# schema.net
KiCad netlist of a schematic drawn in EAGLE
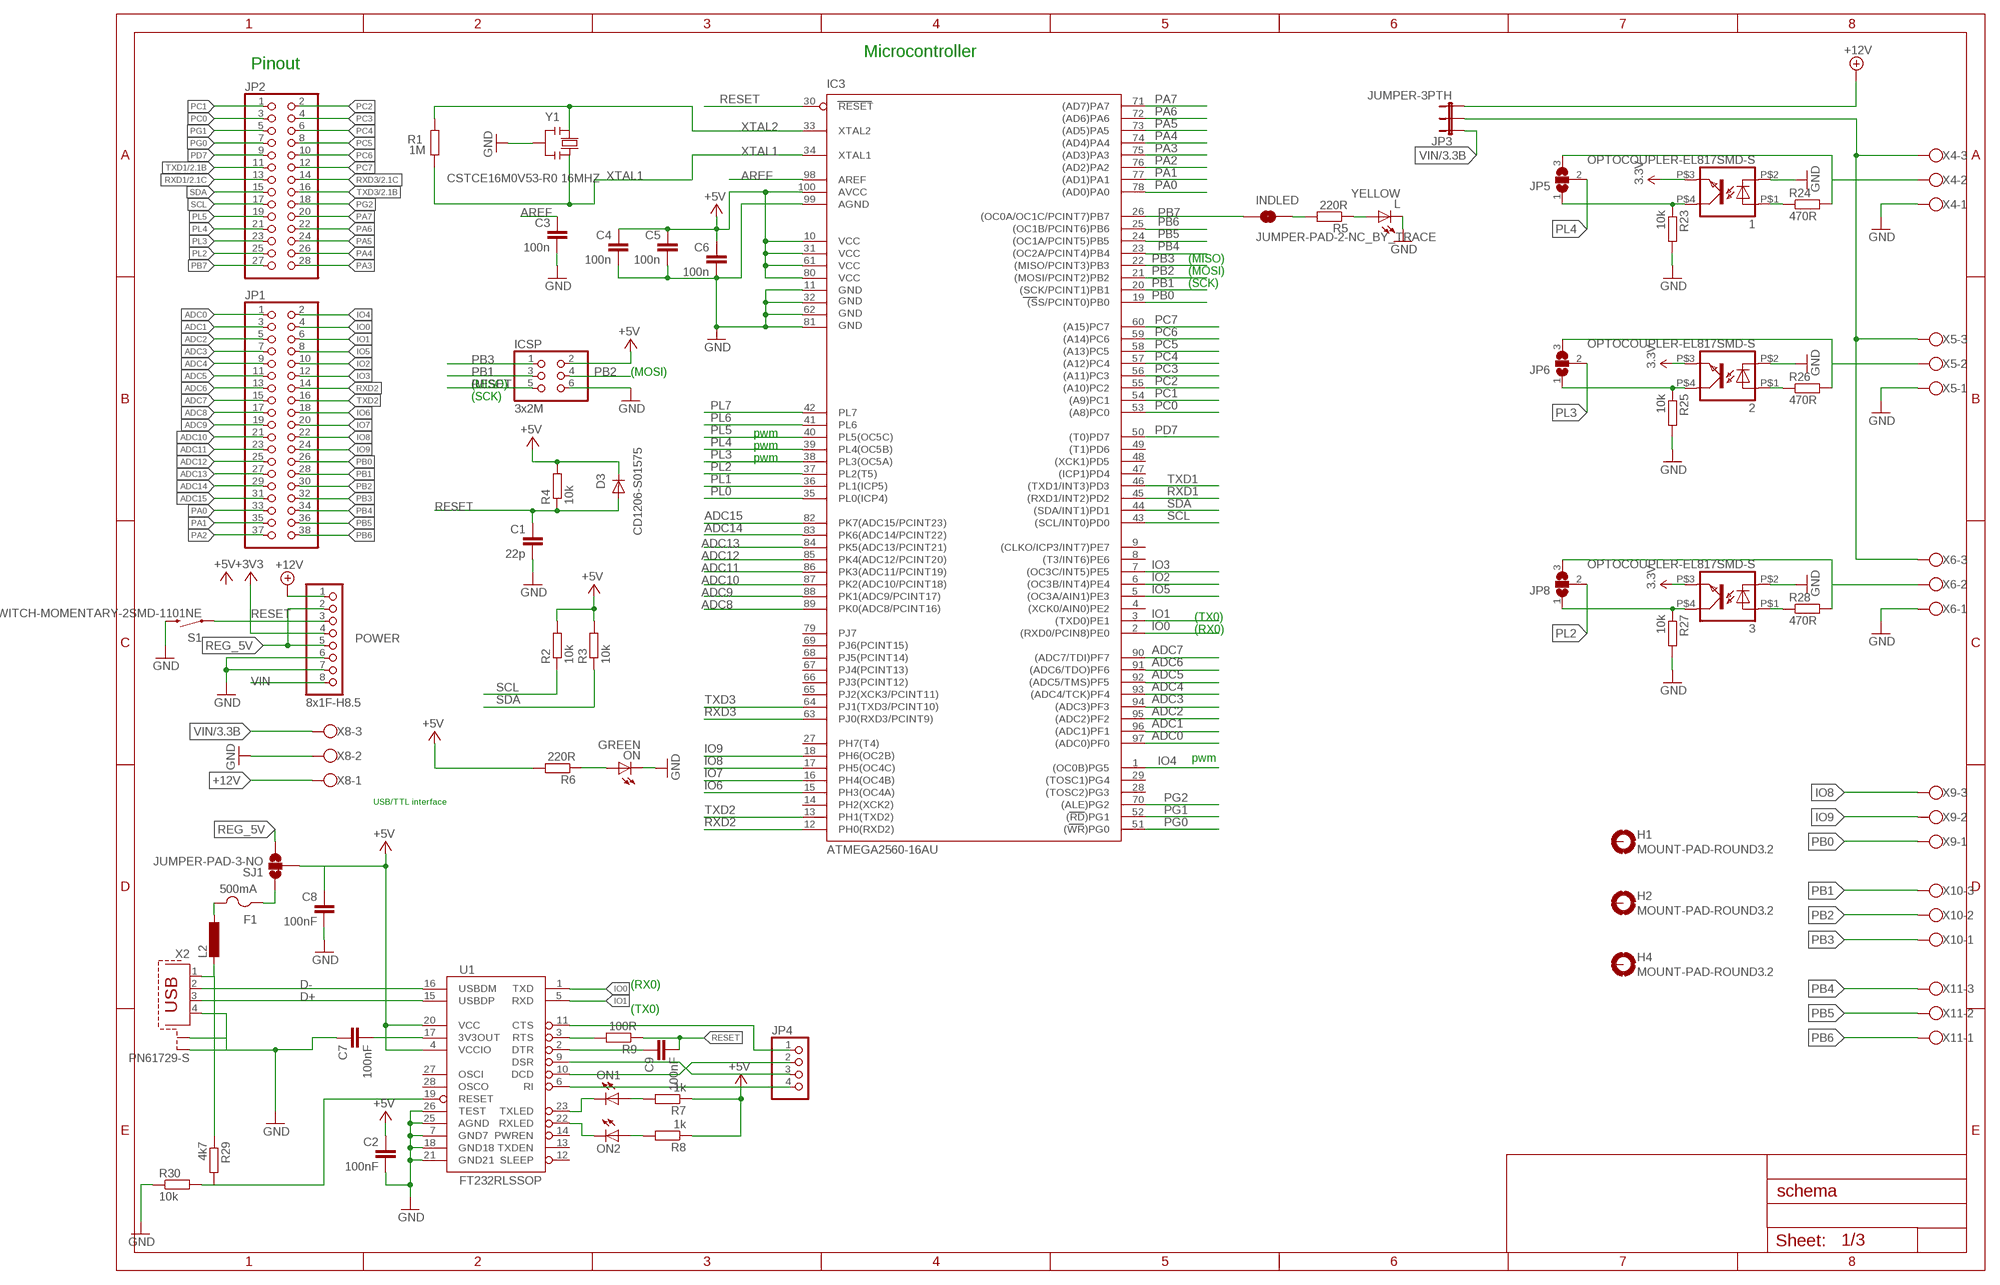
[diagram p0: schematic, sheet 1]
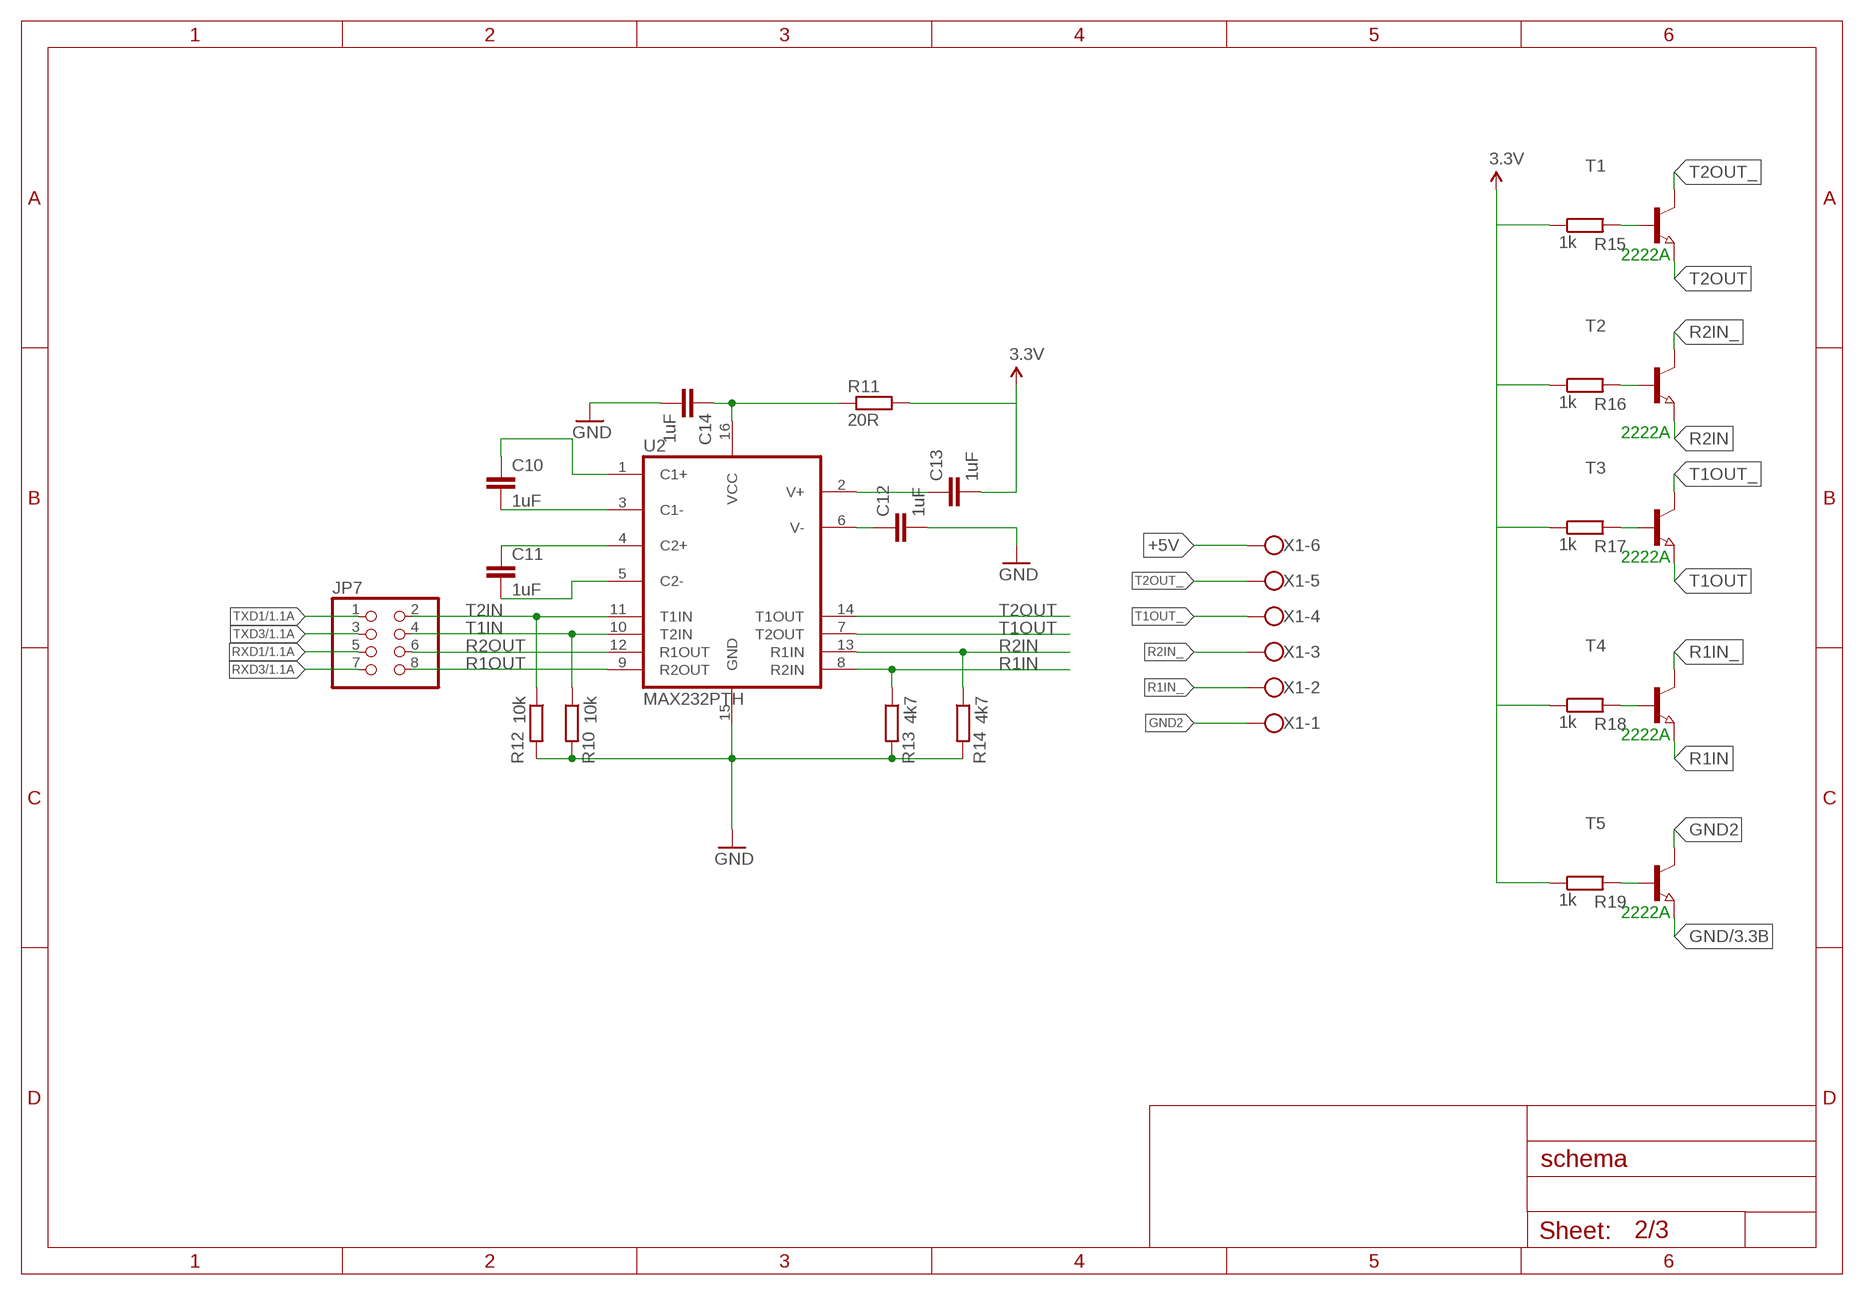
[diagram p1: schematic, sheet 2]
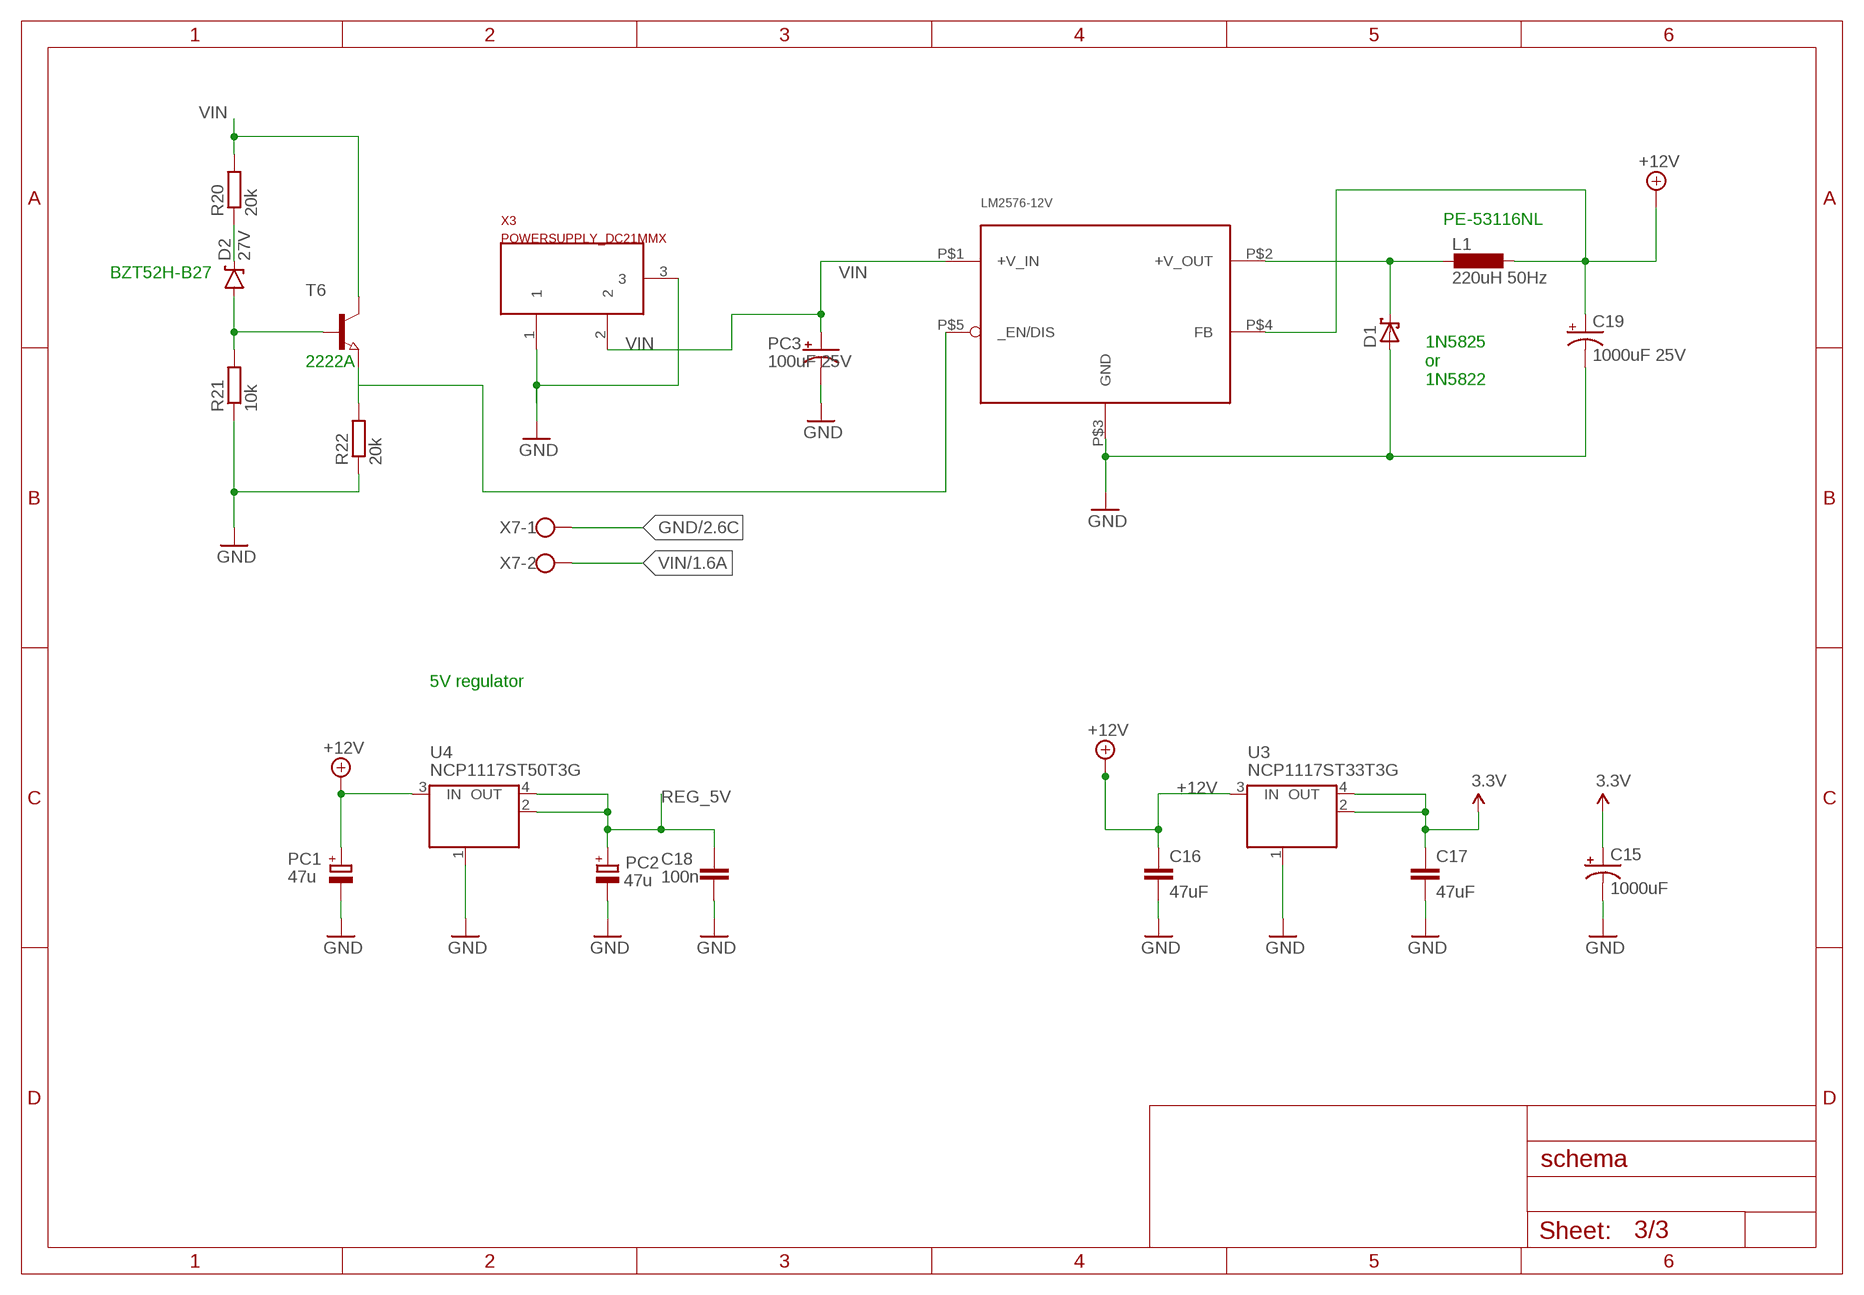
[diagram p2: schematic, sheet 3]

(export (version "E")
  (design (tool "Eeschema 10.0.6"))
  (components
    (comp (ref "C15")
      (value "1000uF")
      (footprint "eagle-import:E5-6")
      (libsource (lib "eagle-import") (part "CPOL-USE5-6"))
    )
    (comp (ref "C16")
      (value "47uF")
      (footprint "eagle-import:C0603")
      (libsource (lib "eagle-import") (part "rcl_C-EUC0603"))
    )
    (comp (ref "C17")
      (value "47uF")
      (footprint "eagle-import:C0603")
      (libsource (lib "eagle-import") (part "rcl_C-EUC0603"))
    )
    (comp (ref "C18")
      (value "100n")
      (footprint "eagle-import:C0603-ROUND")
      (libsource (lib "eagle-import") (part "C-EU0603-RND"))
    )
    (comp (ref "C19")
      (value "1000uF 25V")
      (footprint "eagle-import:E5-6")
      (libsource (lib "eagle-import") (part "CPOL-USE5-6"))
    )
    (comp (ref "D1")
      (value "1N5908")
      (footprint "eagle-import:C4111-15")
      (libsource (lib "eagle-import") (part "1N5908"))
    )
    (comp (ref "D2")
      (value "27V")
      (footprint "eagle-import:SOD-123")
      (libsource (lib "eagle-import") (part "DIODE-ZENER16V"))
    )
    (comp (ref "L1")
      (value "220uH 50Hz")
      (footprint "eagle-import:KM-4.0")
      (libsource (lib "eagle-import") (part "L-KM4.0"))
    )
    (comp (ref "LM2576-12V")
      (value "LM2576-T05D")
      (footprint "eagle-import:TO220-5_STAGGERED")
      (libsource (lib "eagle-import") (part "LM2576-T05D"))
    )
    (comp (ref "PC1")
      (value "47u")
      (footprint "eagle-import:PANASONIC_D")
      (libsource (lib "eagle-import") (part "CPOL-EUD"))
    )
    (comp (ref "PC2")
      (value "47u")
      (footprint "eagle-import:PANASONIC_D")
      (libsource (lib "eagle-import") (part "CPOL-EUD"))
    )
    (comp (ref "PC3")
      (value "100uF 25V")
      (footprint "eagle-import:E5-6")
      (libsource (lib "eagle-import") (part "CPOL-USE5-6"))
    )
    (comp (ref "R20")
      (value "20k")
      (footprint "eagle-import:R0603")
      (libsource (lib "eagle-import") (part "rcl_R-EU_R0603"))
    )
    (comp (ref "R21")
      (value "10k")
      (footprint "eagle-import:R0603")
      (libsource (lib "eagle-import") (part "rcl_R-EU_R0603"))
    )
    (comp (ref "R22")
      (value "20k")
      (footprint "eagle-import:R0603")
      (libsource (lib "eagle-import") (part "rcl_R-EU_R0603"))
    )
    (comp (ref "T6")
      (value "NPN-TRANSISTOR_SOT23")
      (footprint "eagle-import:SOT23")
      (libsource (lib "eagle-import") (part "NPN-TRANSISTOR_SOT23"))
    )
    (comp (ref "U3")
      (value "NCP1117ST33T3G")
      (footprint "eagle-import:SOT223")
      (libsource (lib "eagle-import") (part "MC33269ST-3.3T3"))
    )
    (comp (ref "U4")
      (value "NCP1117ST50T3G")
      (footprint "eagle-import:SOT223")
      (libsource (lib "eagle-import") (part "MC33269ST-3.3T3"))
    )
    (comp (ref "X3")
      (value "POWERSUPPLY_DC21MMX")
      (footprint "eagle-import:POWERSUPPLY_DC-21MM")
      (libsource (lib "eagle-import") (part "POWERSUPPLY_DC21MMX"))
    )
    (comp (ref "X7")
      (value "W237-102")
      (footprint "eagle-import:W237-102")
      (fields (field (name "MPN") "237-102"))
      (libsource (lib "eagle-import") (part "W237-102"))
    )
    (comp (ref "1")
      (value "OPTOCOUPLER-EL817SMD-S")
      (footprint "eagle-import:SMD-S")
      (libsource (lib "eagle-import") (part "OPTOCOUPLER-EL817SMD-S"))
    )
    (comp (ref "2")
      (value "OPTOCOUPLER-EL817SMD-S")
      (footprint "eagle-import:SMD-S")
      (libsource (lib "eagle-import") (part "OPTOCOUPLER-EL817SMD-S"))
    )
    (comp (ref "3")
      (value "OPTOCOUPLER-EL817SMD-S")
      (footprint "eagle-import:SMD-S")
      (libsource (lib "eagle-import") (part "OPTOCOUPLER-EL817SMD-S"))
    )
    (comp (ref "C1")
      (value "22p")
      (footprint "eagle-import:C0603-ROUND")
      (libsource (lib "eagle-import") (part "C-EU0603-RND"))
    )
    (comp (ref "C2")
      (value "100nF")
      (footprint "eagle-import:C0603-ROUND")
      (libsource (lib "eagle-import") (part "C-EU0603-RND"))
    )
    (comp (ref "C3")
      (value "100n")
      (footprint "eagle-import:C0603-ROUND")
      (libsource (lib "eagle-import") (part "C-EU0603-RND"))
    )
    (comp (ref "C4")
      (value "100n")
      (footprint "eagle-import:C0603-ROUND")
      (libsource (lib "eagle-import") (part "C-EU0603-RND"))
    )
    (comp (ref "C5")
      (value "100n")
      (footprint "eagle-import:C0603-ROUND")
      (libsource (lib "eagle-import") (part "C-EU0603-RND"))
    )
    (comp (ref "C6")
      (value "100n")
      (footprint "eagle-import:C0603-ROUND")
      (libsource (lib "eagle-import") (part "C-EU0603-RND"))
    )
    (comp (ref "C7")
      (value "100nF")
      (footprint "eagle-import:C0603-ROUND")
      (libsource (lib "eagle-import") (part "C-EU0603-RND"))
    )
    (comp (ref "C8")
      (value "100nF")
      (footprint "eagle-import:C0603-ROUND")
      (libsource (lib "eagle-import") (part "C-EU0603-RND"))
    )
    (comp (ref "C9")
      (value "100nF")
      (footprint "eagle-import:C0603-ROUND")
      (libsource (lib "eagle-import") (part "C-EU0603-RND"))
    )
    (comp (ref "D3")
      (value "CD1206-S01575")
      (footprint "eagle-import:MINIMELF")
      (libsource (lib "eagle-import") (part "DIODE-MINIMELF"))
    )
    (comp (ref "F1")
      (value "500mA")
      (footprint "eagle-import:1812")
      (libsource (lib "eagle-import") (part "PTCFUSE-1812"))
    )
    (comp (ref "H1")
      (value "MOUNT-PAD-ROUND3.2")
      (footprint "eagle-import:3,2-PAD")
      (libsource (lib "eagle-import") (part "MOUNT-PAD-ROUND3.2"))
    )
    (comp (ref "H2")
      (value "MOUNT-PAD-ROUND3.2")
      (footprint "eagle-import:3,2-PAD")
      (libsource (lib "eagle-import") (part "MOUNT-PAD-ROUND3.2"))
    )
    (comp (ref "H4")
      (value "MOUNT-PAD-ROUND3.2")
      (footprint "eagle-import:3,2-PAD")
      (libsource (lib "eagle-import") (part "MOUNT-PAD-ROUND3.2"))
    )
    (comp (ref "IC3")
      (value "ATMEGA2560-16AU")
      (footprint "eagle-import:TQFP100")
      (libsource (lib "eagle-import") (part "ATMEGA2560AU2560-16"))
    )
    (comp (ref "ICSP")
      (value "3x2M")
      (footprint "eagle-import:2X03")
      (libsource (lib "eagle-import") (part "PINHD-2X3"))
    )
    (comp (ref "INDLED")
      (value "JUMPER-PAD-2-NC_BY_TRACE")
      (footprint "eagle-import:PAD-JUMPER-2-NC_BY_TRACE_YES_SILK")
      (libsource (lib "eagle-import") (part "JUMPER-PAD-2-NC_BY_TRACE"))
    )
    (comp (ref "JP1")
      (value "PINHD-2X19")
      (footprint "eagle-import:2X19")
      (libsource (lib "eagle-import") (part "PINHD-2X19"))
    )
    (comp (ref "JP2")
      (value "PINHD-2X14")
      (footprint "eagle-import:2X14")
      (libsource (lib "eagle-import") (part "PINHD-2X14"))
    )
    (comp (ref "JP3")
      (value "JUMPER-3PTH")
      (footprint "eagle-import:1X03")
      (libsource (lib "eagle-import") (part "JUMPER-3PTH"))
    )
    (comp (ref "JP4")
      (value "PINHD-1X4")
      (footprint "eagle-import:1X04")
      (libsource (lib "eagle-import") (part "PINHD-1X4"))
    )
    (comp (ref "JP5")
      (value "SJ2W")
      (footprint "eagle-import:SJ_2")
      (libsource (lib "eagle-import") (part "SJ2W"))
    )
    (comp (ref "JP6")
      (value "SJ2W")
      (footprint "eagle-import:SJ_2")
      (libsource (lib "eagle-import") (part "SJ2W"))
    )
    (comp (ref "JP8")
      (value "SJ2W")
      (footprint "eagle-import:SJ_2")
      (libsource (lib "eagle-import") (part "SJ2W"))
    )
    (comp (ref "L")
      (value "YELLOW")
      (footprint "eagle-import:CHIP-LED0805")
      (libsource (lib "eagle-import") (part "LEDCHIP-LED0805"))
    )
    (comp (ref "L2")
      (value "L-EUL1812")
      (footprint "eagle-import:L1812")
      (libsource (lib "eagle-import") (part "L-EUL1812"))
    )
    (comp (ref "ON")
      (value "GREEN")
      (footprint "eagle-import:CHIP-LED0805")
      (libsource (lib "eagle-import") (part "LEDCHIP-LED0805"))
    )
    (comp (ref "ON1")
      (value "GREEN")
      (footprint "eagle-import:CHIP-LED0805")
      (libsource (lib "eagle-import") (part "LEDCHIP-LED0805"))
    )
    (comp (ref "ON2")
      (value "GREEN")
      (footprint "eagle-import:CHIP-LED0805")
      (libsource (lib "eagle-import") (part "LEDCHIP-LED0805"))
    )
    (comp (ref "POWER")
      (value "8x1F-H8.5")
      (footprint "eagle-import:1X08")
      (libsource (lib "eagle-import") (part "PINHD-1X8"))
    )
    (comp (ref "R1")
      (value "1M")
      (footprint "eagle-import:R0603-ROUND")
      (libsource (lib "eagle-import") (part "R-EU_R0603"))
    )
    (comp (ref "R2")
      (value "10k")
      (footprint "eagle-import:R0603")
      (libsource (lib "eagle-import") (part "resistor_R-EU_R0603"))
    )
    (comp (ref "R3")
      (value "10k")
      (footprint "eagle-import:R0603")
      (libsource (lib "eagle-import") (part "resistor_R-EU_R0603"))
    )
    (comp (ref "R4")
      (value "10k")
      (footprint "eagle-import:R0603")
      (libsource (lib "eagle-import") (part "resistor_R-EU_R0603"))
    )
    (comp (ref "R5")
      (value "220R")
      (footprint "eagle-import:R0603")
      (libsource (lib "eagle-import") (part "resistor_R-EU_R0603"))
    )
    (comp (ref "R6")
      (value "220R")
      (footprint "eagle-import:R0603")
      (libsource (lib "eagle-import") (part "resistor_R-EU_R0603"))
    )
    (comp (ref "R7")
      (value "1k")
      (footprint "eagle-import:R0603")
      (libsource (lib "eagle-import") (part "resistor_R-EU_R0603"))
    )
    (comp (ref "R8")
      (value "1k")
      (footprint "eagle-import:R0603")
      (libsource (lib "eagle-import") (part "resistor_R-EU_R0603"))
    )
    (comp (ref "R9")
      (value "100R")
      (footprint "eagle-import:R0603")
      (libsource (lib "eagle-import") (part "resistor_R-EU_R0603"))
    )
    (comp (ref "R23")
      (value "10k")
      (footprint "eagle-import:R0603")
      (libsource (lib "eagle-import") (part "resistor_R-EU_R0603"))
    )
    (comp (ref "R24")
      (value "470R")
      (footprint "eagle-import:R0603")
      (libsource (lib "eagle-import") (part "resistor_R-EU_R0603"))
    )
    (comp (ref "R25")
      (value "10k")
      (footprint "eagle-import:R0603")
      (libsource (lib "eagle-import") (part "resistor_R-EU_R0603"))
    )
    (comp (ref "R26")
      (value "470R")
      (footprint "eagle-import:R0603")
      (libsource (lib "eagle-import") (part "resistor_R-EU_R0603"))
    )
    (comp (ref "R27")
      (value "10k")
      (footprint "eagle-import:R0603")
      (libsource (lib "eagle-import") (part "resistor_R-EU_R0603"))
    )
    (comp (ref "R28")
      (value "470R")
      (footprint "eagle-import:R0603")
      (libsource (lib "eagle-import") (part "resistor_R-EU_R0603"))
    )
    (comp (ref "R29")
      (value "4k7")
      (footprint "eagle-import:R0603")
      (libsource (lib "eagle-import") (part "resistor_R-EU_R0603"))
    )
    (comp (ref "R30")
      (value "10k")
      (footprint "eagle-import:R0603")
      (libsource (lib "eagle-import") (part "resistor_R-EU_R0603"))
    )
    (comp (ref "S1")
      (value "SWITCH-MOMENTARY-2SMD-1101NE")
      (footprint "eagle-import:TACTILE-SWITCH-1101NE")
      (libsource (lib "eagle-import") (part "SWITCH-MOMENTARY-2SMD-1101NE"))
    )
    (comp (ref "SJ1")
      (value "JUMPER-PAD-3-NO")
      (footprint "eagle-import:PAD-JUMPER-3-NO_YES_SILK_FULL_BOX_WIDE_SPACING")
      (libsource (lib "eagle-import") (part "JUMPER-PAD-3-NO"))
    )
    (comp (ref "U1")
      (value "FT232RLSSOP")
      (footprint "eagle-import:SSOP28DB")
      (libsource (lib "eagle-import") (part "FT232RLSSOP"))
    )
    (comp (ref "X2")
      (value "PN61729-S")
      (footprint "eagle-import:PN61729-S")
      (libsource (lib "eagle-import") (part "PN61729-S"))
    )
    (comp (ref "X4")
      (value "W237-103")
      (footprint "eagle-import:W237-103")
      (fields (field (name "MPN") "237-103"))
      (libsource (lib "eagle-import") (part "W237-103"))
    )
    (comp (ref "X5")
      (value "W237-103")
      (footprint "eagle-import:W237-103")
      (fields (field (name "MPN") "237-103"))
      (libsource (lib "eagle-import") (part "W237-103"))
    )
    (comp (ref "X6")
      (value "W237-103")
      (footprint "eagle-import:W237-103")
      (fields (field (name "MPN") "237-103"))
      (libsource (lib "eagle-import") (part "W237-103"))
    )
    (comp (ref "X8")
      (value "W237-103")
      (footprint "eagle-import:W237-103")
      (fields (field (name "MPN") "237-103"))
      (libsource (lib "eagle-import") (part "W237-103"))
    )
    (comp (ref "X9")
      (value "W237-103")
      (footprint "eagle-import:W237-103")
      (fields (field (name "MPN") "237-103"))
      (libsource (lib "eagle-import") (part "W237-103"))
    )
    (comp (ref "X10")
      (value "W237-103")
      (footprint "eagle-import:W237-103")
      (fields (field (name "MPN") "237-103"))
      (libsource (lib "eagle-import") (part "W237-103"))
    )
    (comp (ref "X11")
      (value "W237-103")
      (footprint "eagle-import:W237-103")
      (fields (field (name "MPN") "237-103"))
      (libsource (lib "eagle-import") (part "W237-103"))
    )
    (comp (ref "Y1")
      (value "CSTCE16M0V53-R0 16MHZ")
      (footprint "eagle-import:RESONATOR")
      (libsource (lib "eagle-import") (part "RESONATORMU"))
    )
    (comp (ref "C10")
      (value "1uF")
      (footprint "eagle-import:C0603")
      (libsource (lib "eagle-import") (part "rcl_C-EUC0603"))
    )
    (comp (ref "C11")
      (value "1uF")
      (footprint "eagle-import:C0603")
      (libsource (lib "eagle-import") (part "rcl_C-EUC0603"))
    )
    (comp (ref "C12")
      (value "1uF")
      (footprint "eagle-import:C0603")
      (libsource (lib "eagle-import") (part "rcl_C-EUC0603"))
    )
    (comp (ref "C13")
      (value "1uF")
      (footprint "eagle-import:C0603")
      (libsource (lib "eagle-import") (part "rcl_C-EUC0603"))
    )
    (comp (ref "C14")
      (value "1uF")
      (footprint "eagle-import:C0603")
      (libsource (lib "eagle-import") (part "rcl_C-EUC0603"))
    )
    (comp (ref "JP7")
      (value "PINHD-2X4")
      (footprint "eagle-import:2X04")
      (libsource (lib "eagle-import") (part "PINHD-2X4"))
    )
    (comp (ref "R10")
      (value "10k")
      (footprint "eagle-import:R0603")
      (libsource (lib "eagle-import") (part "rcl_R-EU_R0603"))
    )
    (comp (ref "R11")
      (value "20R")
      (footprint "eagle-import:R0603")
      (libsource (lib "eagle-import") (part "rcl_R-EU_R0603"))
    )
    (comp (ref "R12")
      (value "10k")
      (footprint "eagle-import:R0603")
      (libsource (lib "eagle-import") (part "rcl_R-EU_R0603"))
    )
    (comp (ref "R13")
      (value "4k7")
      (footprint "eagle-import:R0603")
      (libsource (lib "eagle-import") (part "rcl_R-EU_R0603"))
    )
    (comp (ref "R14")
      (value "4k7")
      (footprint "eagle-import:R0603")
      (libsource (lib "eagle-import") (part "rcl_R-EU_R0603"))
    )
    (comp (ref "R15")
      (value "1k")
      (footprint "eagle-import:R0603")
      (libsource (lib "eagle-import") (part "rcl_R-EU_R0603"))
    )
    (comp (ref "R16")
      (value "1k")
      (footprint "eagle-import:R0603")
      (libsource (lib "eagle-import") (part "rcl_R-EU_R0603"))
    )
    (comp (ref "R17")
      (value "1k")
      (footprint "eagle-import:R0603")
      (libsource (lib "eagle-import") (part "rcl_R-EU_R0603"))
    )
    (comp (ref "R18")
      (value "1k")
      (footprint "eagle-import:R0603")
      (libsource (lib "eagle-import") (part "rcl_R-EU_R0603"))
    )
    (comp (ref "R19")
      (value "1k")
      (footprint "eagle-import:R0603")
      (libsource (lib "eagle-import") (part "rcl_R-EU_R0603"))
    )
    (comp (ref "T1")
      (value "NPN-TRANSISTOR_SOT23")
      (footprint "eagle-import:SOT23")
      (libsource (lib "eagle-import") (part "NPN-TRANSISTOR_SOT23"))
    )
    (comp (ref "T2")
      (value "NPN-TRANSISTOR_SOT23")
      (footprint "eagle-import:SOT23")
      (libsource (lib "eagle-import") (part "NPN-TRANSISTOR_SOT23"))
    )
    (comp (ref "T3")
      (value "NPN-TRANSISTOR_SOT23")
      (footprint "eagle-import:SOT23")
      (libsource (lib "eagle-import") (part "NPN-TRANSISTOR_SOT23"))
    )
    (comp (ref "T4")
      (value "NPN-TRANSISTOR_SOT23")
      (footprint "eagle-import:SOT23")
      (libsource (lib "eagle-import") (part "NPN-TRANSISTOR_SOT23"))
    )
    (comp (ref "T5")
      (value "NPN-TRANSISTOR_SOT23")
      (footprint "eagle-import:SOT23")
      (libsource (lib "eagle-import") (part "NPN-TRANSISTOR_SOT23"))
    )
    (comp (ref "U2")
      (value "MAX232PTH")
      (footprint "eagle-import:DIL16")
      (libsource (lib "eagle-import") (part "MAX232PTH"))
    )
    (comp (ref "X1")
      (value "W237-6")
      (footprint "eagle-import:W237-6")
      (libsource (lib "eagle-import") (part "W237-6"))
    )
  )
  (nets
    (net (code "1") (name "+5V") (class "Default")
      (node (ref "C2") (pin "1") (pinfunction "1_1") (pintype "passive"))
      (node (ref "C4") (pin "1") (pinfunction "1_1") (pintype "passive"))
      (node (ref "C5") (pin "1") (pinfunction "1_1") (pintype "passive"))
      (node (ref "C6") (pin "1") (pinfunction "1_1") (pintype "passive"))
      (node (ref "C8") (pin "1") (pinfunction "1_1") (pintype "passive"))
      (node (ref "D3") (pin "C") (pinfunction "C_C") (pintype "passive"))
      (node (ref "IC3") (pin "10") (pinfunction "VCC_10") (pintype "power_in"))
      (node (ref "IC3") (pin "100") (pinfunction "AVCC_100") (pintype "power_in"))
      (node (ref "IC3") (pin "31") (pinfunction "VCC1_31") (pintype "power_in"))
      (node (ref "IC3") (pin "61") (pinfunction "VCC2_61") (pintype "power_in"))
      (node (ref "IC3") (pin "80") (pinfunction "VCC3_80") (pintype "power_in"))
      (node (ref "ICSP") (pin "2") (pinfunction "2_2") (pintype "passive"))
      (node (ref "R2") (pin "2") (pinfunction "2_2") (pintype "passive"))
      (node (ref "R3") (pin "2") (pinfunction "2_2") (pintype "passive"))
      (node (ref "R4") (pin "2") (pinfunction "2_2") (pintype "passive"))
      (node (ref "R6") (pin "2") (pinfunction "2_2") (pintype "passive"))
      (node (ref "R7") (pin "1") (pinfunction "1_1") (pintype "passive"))
      (node (ref "R8") (pin "1") (pinfunction "1_1") (pintype "passive"))
      (node (ref "SJ1") (pin "2") (pinfunction "2_2") (pintype "passive"))
      (node (ref "U1") (pin "20") (pinfunction "VCC_20") (pintype "power_in"))
      (node (ref "U1") (pin "4") (pinfunction "VCCIO_4") (pintype "power_in"))
      (node (ref "X1") (pin "6") (pinfunction "KL_6") (pintype "passive"))
    )
    (net (code "2") (name "+12V") (class "Default")
      (node (ref "C16") (pin "1") (pinfunction "1_1") (pintype "passive"))
      (node (ref "C19") (pin "+") (pinfunction "+_+") (pintype "passive"))
      (node (ref "JP3") (pin "3") (pinfunction "3_3") (pintype "passive"))
      (node (ref "L1") (pin "P$2") (pinfunction "2_P$2") (pintype "passive"))
      (node (ref "LM2576-12V") (pin "P$4") (pinfunction "FB_P$4") (pintype "input"))
      (node (ref "PC1") (pin "+") (pinfunction "+_+") (pintype "passive"))
      (node (ref "POWER") (pin "1") (pinfunction "1_1") (pintype "passive"))
      (node (ref "U3") (pin "3") (pinfunction "IN_3") (pintype "input"))
      (node (ref "U4") (pin "3") (pinfunction "IN_3") (pintype "input"))
      (node (ref "X8") (pin "1") (pinfunction "KL_1") (pintype "passive"))
    )
    (net (code "3") (name "3.3V") (class "Default")
      (node (ref "1") (pin "P$3") (pinfunction "3_P$3") (pintype "passive"))
      (node (ref "2") (pin "P$3") (pinfunction "3_P$3") (pintype "passive"))
      (node (ref "3") (pin "P$3") (pinfunction "3_P$3") (pintype "passive"))
      (node (ref "C13") (pin "2") (pinfunction "2_2") (pintype "passive"))
      (node (ref "C15") (pin "+") (pinfunction "+_+") (pintype "passive"))
      (node (ref "C17") (pin "1") (pinfunction "1_1") (pintype "passive"))
      (node (ref "POWER") (pin "4") (pinfunction "4_4") (pintype "passive"))
      (node (ref "R11") (pin "2") (pinfunction "2_2") (pintype "passive"))
      (node (ref "R15") (pin "1") (pinfunction "1_1") (pintype "passive"))
      (node (ref "R16") (pin "1") (pinfunction "1_1") (pintype "passive"))
      (node (ref "R17") (pin "1") (pinfunction "1_1") (pintype "passive"))
      (node (ref "R18") (pin "1") (pinfunction "1_1") (pintype "passive"))
      (node (ref "R19") (pin "1") (pinfunction "1_1") (pintype "passive"))
      (node (ref "U3") (pin "2") (pinfunction "OUT_2") (pintype "passive"))
      (node (ref "U3") (pin "4") (pinfunction "OUT_4") (pintype "passive"))
    )
    (net (code "4") (name "ADC0") (class "Default")
      (node (ref "IC3") (pin "97") (pinfunction "(ADC0)PF0_97") (pintype "bidirectional"))
      (node (ref "JP1") (pin "1") (pinfunction "1_1") (pintype "passive"))
    )
    (net (code "5") (name "ADC1") (class "Default")
      (node (ref "IC3") (pin "96") (pinfunction "(ADC1)PF1_96") (pintype "bidirectional"))
      (node (ref "JP1") (pin "3") (pinfunction "3_3") (pintype "passive"))
    )
    (net (code "6") (name "ADC2") (class "Default")
      (node (ref "IC3") (pin "95") (pinfunction "(ADC2)PF2_95") (pintype "bidirectional"))
      (node (ref "JP1") (pin "5") (pinfunction "5_5") (pintype "passive"))
    )
    (net (code "7") (name "ADC3") (class "Default")
      (node (ref "IC3") (pin "94") (pinfunction "(ADC3)PF3_94") (pintype "bidirectional"))
      (node (ref "JP1") (pin "7") (pinfunction "7_7") (pintype "passive"))
    )
    (net (code "8") (name "ADC4") (class "Default")
      (node (ref "IC3") (pin "93") (pinfunction "(ADC4/TCK)PF4_93") (pintype "bidirectional"))
      (node (ref "JP1") (pin "9") (pinfunction "9_9") (pintype "passive"))
    )
    (net (code "9") (name "ADC5") (class "Default")
      (node (ref "IC3") (pin "92") (pinfunction "(ADC5/TMS)PF5_92") (pintype "bidirectional"))
      (node (ref "JP1") (pin "11") (pinfunction "11_11") (pintype "passive"))
    )
    (net (code "10") (name "ADC6") (class "Default")
      (node (ref "IC3") (pin "91") (pinfunction "(ADC6/TDO)PF6_91") (pintype "bidirectional"))
      (node (ref "JP1") (pin "13") (pinfunction "13_13") (pintype "passive"))
    )
    (net (code "11") (name "ADC7") (class "Default")
      (node (ref "IC3") (pin "90") (pinfunction "(ADC7/TDI)PF7_90") (pintype "bidirectional"))
      (node (ref "JP1") (pin "15") (pinfunction "15_15") (pintype "passive"))
    )
    (net (code "12") (name "ADC8") (class "Default")
      (node (ref "IC3") (pin "89") (pinfunction "PK0(ADC8/PCINT16)_89") (pintype "bidirectional"))
      (node (ref "JP1") (pin "17") (pinfunction "17_17") (pintype "passive"))
    )
    (net (code "13") (name "ADC9") (class "Default")
      (node (ref "IC3") (pin "88") (pinfunction "PK1(ADC9/PCINT17)_88") (pintype "bidirectional"))
      (node (ref "JP1") (pin "19") (pinfunction "19_19") (pintype "passive"))
    )
    (net (code "14") (name "ADC10") (class "Default")
      (node (ref "IC3") (pin "87") (pinfunction "PK2(ADC10/PCINT18)_87") (pintype "bidirectional"))
      (node (ref "JP1") (pin "21") (pinfunction "21_21") (pintype "passive"))
    )
    (net (code "15") (name "ADC11") (class "Default")
      (node (ref "IC3") (pin "86") (pinfunction "PK3(ADC11/PCINT19)_86") (pintype "bidirectional"))
      (node (ref "JP1") (pin "23") (pinfunction "23_23") (pintype "passive"))
    )
    (net (code "16") (name "ADC12") (class "Default")
      (node (ref "IC3") (pin "85") (pinfunction "PK4(ADC12/PCINT20)_85") (pintype "bidirectional"))
      (node (ref "JP1") (pin "25") (pinfunction "25_25") (pintype "passive"))
    )
    (net (code "17") (name "ADC13") (class "Default")
      (node (ref "IC3") (pin "84") (pinfunction "PK5(ADC13/PCINT21)_84") (pintype "bidirectional"))
      (node (ref "JP1") (pin "27") (pinfunction "27_27") (pintype "passive"))
    )
    (net (code "18") (name "ADC14") (class "Default")
      (node (ref "IC3") (pin "83") (pinfunction "PK6(ADC14/PCINT22)_83") (pintype "bidirectional"))
      (node (ref "JP1") (pin "29") (pinfunction "29_29") (pintype "passive"))
    )
    (net (code "19") (name "ADC15") (class "Default")
      (node (ref "IC3") (pin "82") (pinfunction "PK7(ADC15/PCINT23)_82") (pintype "bidirectional"))
      (node (ref "JP1") (pin "31") (pinfunction "31_31") (pintype "passive"))
    )
    (net (code "20") (name "AREF") (class "Default")
      (node (ref "C3") (pin "1") (pinfunction "1_1") (pintype "passive"))
      (node (ref "IC3") (pin "98") (pinfunction "AREF_98") (pintype "bidirectional"))
    )
    (net (code "21") (name "D+") (class "Default")
      (node (ref "U1") (pin "15") (pinfunction "USBDP_15") (pintype "bidirectional"))
      (node (ref "X2") (pin "3") (pinfunction "3_3") (pintype "passive"))
    )
    (net (code "22") (name "D-") (class "Default")
      (node (ref "U1") (pin "16") (pinfunction "USBDM_16") (pintype "bidirectional"))
      (node (ref "X2") (pin "2") (pinfunction "2_2") (pintype "passive"))
    )
    (net (code "23") (name "GND") (class "Default")
      (node (ref "1") (pin "P$2") (pinfunction "2_P$2") (pintype "passive"))
      (node (ref "2") (pin "P$2") (pinfunction "2_P$2") (pintype "passive"))
      (node (ref "3") (pin "P$2") (pinfunction "2_P$2") (pintype "passive"))
      (node (ref "C1") (pin "2") (pinfunction "2_2") (pintype "passive"))
      (node (ref "C12") (pin "2") (pinfunction "2_2") (pintype "passive"))
      (node (ref "C14") (pin "2") (pinfunction "2_2") (pintype "passive"))
      (node (ref "C15") (pin "-") (pinfunction "-_-") (pintype "passive"))
      (node (ref "C16") (pin "2") (pinfunction "2_2") (pintype "passive"))
      (node (ref "C17") (pin "2") (pinfunction "2_2") (pintype "passive"))
      (node (ref "C18") (pin "1") (pinfunction "1_1") (pintype "passive"))
      (node (ref "C19") (pin "-") (pinfunction "-_-") (pintype "passive"))
      (node (ref "C2") (pin "2") (pinfunction "2_2") (pintype "passive"))
      (node (ref "C3") (pin "2") (pinfunction "2_2") (pintype "passive"))
      (node (ref "C4") (pin "2") (pinfunction "2_2") (pintype "passive"))
      (node (ref "C5") (pin "2") (pinfunction "2_2") (pintype "passive"))
      (node (ref "C6") (pin "2") (pinfunction "2_2") (pintype "passive"))
      (node (ref "C7") (pin "1") (pinfunction "1_1") (pintype "passive"))
      (node (ref "C8") (pin "2") (pinfunction "2_2") (pintype "passive"))
      (node (ref "D1") (pin "A") (pinfunction "A_A") (pintype "passive"))
      (node (ref "IC3") (pin "11") (pinfunction "GND_11") (pintype "power_in"))
      (node (ref "IC3") (pin "32") (pinfunction "GND1_32") (pintype "power_in"))
      (node (ref "IC3") (pin "62") (pinfunction "GND2_62") (pintype "power_in"))
      (node (ref "IC3") (pin "81") (pinfunction "GND3_81") (pintype "power_in"))
      (node (ref "IC3") (pin "99") (pinfunction "AGND_99") (pintype "power_in"))
      (node (ref "ICSP") (pin "6") (pinfunction "6_6") (pintype "passive"))
      (node (ref "L") (pin "C") (pinfunction "C_C") (pintype "passive"))
      (node (ref "LM2576-12V") (pin "P$3") (pinfunction "GND_P$3") (pintype "power_in"))
      (node (ref "ON") (pin "C") (pinfunction "C_C") (pintype "passive"))
      (node (ref "PC1") (pin "-") (pinfunction "-_-") (pintype "passive"))
      (node (ref "PC2") (pin "-") (pinfunction "-_-") (pintype "passive"))
      (node (ref "PC3") (pin "-") (pinfunction "-_-") (pintype "passive"))
      (node (ref "POWER") (pin "6") (pinfunction "6_6") (pintype "passive"))
      (node (ref "POWER") (pin "7") (pinfunction "7_7") (pintype "passive"))
      (node (ref "R10") (pin "2") (pinfunction "2_2") (pintype "passive"))
      (node (ref "R12") (pin "2") (pinfunction "2_2") (pintype "passive"))
      (node (ref "R13") (pin "2") (pinfunction "2_2") (pintype "passive"))
      (node (ref "R14") (pin "2") (pinfunction "2_2") (pintype "passive"))
      (node (ref "R21") (pin "1") (pinfunction "1_1") (pintype "passive"))
      (node (ref "R22") (pin "1") (pinfunction "1_1") (pintype "passive"))
      (node (ref "R23") (pin "2") (pinfunction "2_2") (pintype "passive"))
      (node (ref "R25") (pin "2") (pinfunction "2_2") (pintype "passive"))
      (node (ref "R27") (pin "2") (pinfunction "2_2") (pintype "passive"))
      (node (ref "R30") (pin "1") (pinfunction "1_1") (pintype "passive"))
      (node (ref "S1") (pin "2") (pinfunction "2_2") (pintype "passive"))
      (node (ref "T5") (pin "2") (pinfunction "E_2") (pintype "passive"))
      (node (ref "U1") (pin "18") (pinfunction "GND18_18") (pintype "power_in"))
      (node (ref "U1") (pin "21") (pinfunction "GND21_21") (pintype "power_in"))
      (node (ref "U1") (pin "25") (pinfunction "AGND_25") (pintype "power_in"))
      (node (ref "U1") (pin "26") (pinfunction "TEST_26") (pintype "input"))
      (node (ref "U1") (pin "7") (pinfunction "GND7_7") (pintype "power_in"))
      (node (ref "U2") (pin "15") (pinfunction "GND_15") (pintype "bidirectional"))
      (node (ref "U3") (pin "1") (pinfunction "GND/ADJ_1") (pintype "input"))
      (node (ref "U4") (pin "1") (pinfunction "GND/ADJ_1") (pintype "input"))
      (node (ref "X2") (pin "4") (pinfunction "4_4") (pintype "passive"))
      (node (ref "X2") (pin "S1") (pinfunction "S1_S1") (pintype "passive"))
      (node (ref "X2") (pin "S2") (pinfunction "S2_S2") (pintype "passive"))
      (node (ref "X3") (pin "1") (pinfunction "1_1") (pintype "power_in"))
      (node (ref "X3") (pin "3") (pinfunction "3_3") (pintype "power_in"))
      (node (ref "X4") (pin "1") (pinfunction "KL_1") (pintype "passive"))
      (node (ref "X5") (pin "1") (pinfunction "KL_1") (pintype "passive"))
      (node (ref "X6") (pin "1") (pinfunction "KL_1") (pintype "passive"))
      (node (ref "X7") (pin "1") (pinfunction "KL_1") (pintype "passive"))
      (node (ref "X8") (pin "2") (pinfunction "KL_2") (pintype "passive"))
      (node (ref "Y1") (pin "2") (pinfunction "2_2") (pintype "passive"))
    )
    (net (code "24") (name "GND2") (class "Default")
      (node (ref "T5") (pin "3") (pinfunction "C_3") (pintype "passive"))
      (node (ref "X1") (pin "1") (pinfunction "KL_1") (pintype "passive"))
    )
    (net (code "25") (name "IO0") (class "Default")
      (node (ref "IC3") (pin "2") (pinfunction "(RXD0/PCIN8)PE0_2") (pintype "bidirectional"))
      (node (ref "JP1") (pin "4") (pinfunction "4_4") (pintype "passive"))
      (node (ref "U1") (pin "1") (pinfunction "TXD_1") (pintype "output"))
    )
    (net (code "26") (name "IO1") (class "Default")
      (node (ref "IC3") (pin "3") (pinfunction "(TXD0)PE1_3") (pintype "bidirectional"))
      (node (ref "JP1") (pin "6") (pinfunction "6_6") (pintype "passive"))
      (node (ref "U1") (pin "5") (pinfunction "RXD_5") (pintype "input"))
    )
    (net (code "27") (name "IO2") (class "Default")
      (node (ref "IC3") (pin "6") (pinfunction "(OC3B/INT4)PE4_6") (pintype "bidirectional"))
      (node (ref "JP1") (pin "10") (pinfunction "10_10") (pintype "passive"))
    )
    (net (code "28") (name "IO3") (class "Default")
      (node (ref "IC3") (pin "7") (pinfunction "(OC3C/INT5)PE5_7") (pintype "bidirectional"))
      (node (ref "JP1") (pin "12") (pinfunction "12_12") (pintype "passive"))
    )
    (net (code "29") (name "IO4") (class "Default")
      (node (ref "IC3") (pin "1") (pinfunction "(OC0B)PG5_1") (pintype "bidirectional"))
      (node (ref "JP1") (pin "2") (pinfunction "2_2") (pintype "passive"))
    )
    (net (code "30") (name "IO5") (class "Default")
      (node (ref "IC3") (pin "5") (pinfunction "(OC3A/AIN1)PE3_5") (pintype "bidirectional"))
      (node (ref "JP1") (pin "8") (pinfunction "8_8") (pintype "passive"))
    )
    (net (code "31") (name "IO6") (class "Default")
      (node (ref "IC3") (pin "15") (pinfunction "PH3(OC4A)_15") (pintype "bidirectional"))
      (node (ref "JP1") (pin "18") (pinfunction "18_18") (pintype "passive"))
    )
    (net (code "32") (name "IO7") (class "Default")
      (node (ref "IC3") (pin "16") (pinfunction "PH4(OC4B)_16") (pintype "bidirectional"))
      (node (ref "JP1") (pin "20") (pinfunction "20_20") (pintype "passive"))
    )
    (net (code "33") (name "IO8") (class "Default")
      (node (ref "IC3") (pin "17") (pinfunction "PH5(OC4C)_17") (pintype "bidirectional"))
      (node (ref "JP1") (pin "22") (pinfunction "22_22") (pintype "passive"))
      (node (ref "X9") (pin "3") (pinfunction "KL_3") (pintype "passive"))
    )
    (net (code "34") (name "IO9") (class "Default")
      (node (ref "IC3") (pin "18") (pinfunction "PH6(OC2B)_18") (pintype "bidirectional"))
      (node (ref "JP1") (pin "24") (pinfunction "24_24") (pintype "passive"))
      (node (ref "X9") (pin "2") (pinfunction "KL_2") (pintype "passive"))
    )
    (net (code "35") (name "Net-(1-1)") (class "Default")
      (node (ref "1") (pin "P$1") (pinfunction "1_P$1") (pintype "passive"))
      (node (ref "R24") (pin "1") (pinfunction "1_1") (pintype "passive"))
    )
    (net (code "36") (name "Net-(1-4)") (class "Default")
      (node (ref "1") (pin "P$4") (pinfunction "4_P$4") (pintype "passive"))
      (node (ref "JP5") (pin "1") (pinfunction "1_1") (pintype "passive"))
      (node (ref "R23") (pin "1") (pinfunction "1_1") (pintype "passive"))
    )
    (net (code "37") (name "Net-(2-1)") (class "Default")
      (node (ref "2") (pin "P$1") (pinfunction "1_P$1") (pintype "passive"))
      (node (ref "R26") (pin "1") (pinfunction "1_1") (pintype "passive"))
    )
    (net (code "38") (name "Net-(2-4)") (class "Default")
      (node (ref "2") (pin "P$4") (pinfunction "4_P$4") (pintype "passive"))
      (node (ref "JP6") (pin "1") (pinfunction "1_1") (pintype "passive"))
      (node (ref "R25") (pin "1") (pinfunction "1_1") (pintype "passive"))
    )
    (net (code "39") (name "Net-(3-1)") (class "Default")
      (node (ref "3") (pin "P$1") (pinfunction "1_P$1") (pintype "passive"))
      (node (ref "R28") (pin "1") (pinfunction "1_1") (pintype "passive"))
    )
    (net (code "40") (name "Net-(3-4)") (class "Default")
      (node (ref "3") (pin "P$4") (pinfunction "4_P$4") (pintype "passive"))
      (node (ref "JP8") (pin "1") (pinfunction "1_1") (pintype "passive"))
      (node (ref "R27") (pin "1") (pinfunction "1_1") (pintype "passive"))
    )
    (net (code "41") (name "Net-(D2-PadC)") (class "Default")
      (node (ref "D2") (pin "C") (pinfunction "C_C") (pintype "passive"))
      (node (ref "R20") (pin "1") (pinfunction "1_1") (pintype "passive"))
    )
    (net (code "42") (name "Net-(F1-Pad1)") (class "Default")
      (node (ref "F1") (pin "1") (pinfunction "1_1") (pintype "passive"))
      (node (ref "SJ1") (pin "1") (pinfunction "1_1") (pintype "passive"))
    )
    (net (code "43") (name "Net-(F1-Pad2)") (class "Default")
      (node (ref "F1") (pin "2") (pinfunction "2_2") (pintype "passive"))
      (node (ref "L2") (pin "1") (pinfunction "1_1") (pintype "passive"))
    )
    (net (code "44") (name "Net-(INDLED-Pad2)") (class "Default")
      (node (ref "INDLED") (pin "2") (pinfunction "2_2") (pintype "passive"))
      (node (ref "R5") (pin "2") (pinfunction "2_2") (pintype "passive"))
    )
    (net (code "45") (name "Net-(L-PadA)") (class "Default")
      (node (ref "L") (pin "A") (pinfunction "A_A") (pintype "passive"))
      (node (ref "R5") (pin "1") (pinfunction "1_1") (pintype "passive"))
    )
    (net (code "46") (name "Net-(L1-1)") (class "Default")
      (node (ref "D1") (pin "C") (pinfunction "C_C") (pintype "passive"))
      (node (ref "L1") (pin "P$1") (pinfunction "1_P$1") (pintype "passive"))
      (node (ref "LM2576-12V") (pin "P$2") (pinfunction "+V_OUT_P$2") (pintype "output"))
    )
    (net (code "47") (name "Net-(L2-Pad2)") (class "Default")
      (node (ref "L2") (pin "2") (pinfunction "2_2") (pintype "passive"))
      (node (ref "R29") (pin "1") (pinfunction "1_1") (pintype "passive"))
      (node (ref "X2") (pin "1") (pinfunction "1_1") (pintype "passive"))
    )
    (net (code "48") (name "Net-(LM2576-12V-_EN{slash}DIS)") (class "Default")
      (node (ref "LM2576-12V") (pin "P$5") (pinfunction "_EN/DIS_P$5") (pintype "input"))
      (node (ref "R22") (pin "2") (pinfunction "2_2") (pintype "passive"))
      (node (ref "T6") (pin "2") (pinfunction "E_2") (pintype "passive"))
    )
    (net (code "49") (name "Net-(ON-PadA)") (class "Default")
      (node (ref "ON") (pin "A") (pinfunction "A_A") (pintype "passive"))
      (node (ref "R6") (pin "1") (pinfunction "1_1") (pintype "passive"))
    )
    (net (code "50") (name "Net-(ON1-PadA)") (class "Default")
      (node (ref "ON1") (pin "A") (pinfunction "A_A") (pintype "passive"))
      (node (ref "R7") (pin "2") (pinfunction "2_2") (pintype "passive"))
    )
    (net (code "51") (name "Net-(ON2-PadA)") (class "Default")
      (node (ref "ON2") (pin "A") (pinfunction "A_A") (pintype "passive"))
      (node (ref "R8") (pin "2") (pinfunction "2_2") (pintype "passive"))
    )
    (net (code "52") (name "Net-(T1-B)") (class "Default")
      (node (ref "R15") (pin "2") (pinfunction "2_2") (pintype "passive"))
      (node (ref "T1") (pin "1") (pinfunction "B_1") (pintype "passive"))
    )
    (net (code "53") (name "Net-(T2-B)") (class "Default")
      (node (ref "R16") (pin "2") (pinfunction "2_2") (pintype "passive"))
      (node (ref "T2") (pin "1") (pinfunction "B_1") (pintype "passive"))
    )
    (net (code "54") (name "Net-(T3-B)") (class "Default")
      (node (ref "R17") (pin "2") (pinfunction "2_2") (pintype "passive"))
      (node (ref "T3") (pin "1") (pinfunction "B_1") (pintype "passive"))
    )
    (net (code "55") (name "Net-(T4-B)") (class "Default")
      (node (ref "R18") (pin "2") (pinfunction "2_2") (pintype "passive"))
      (node (ref "T4") (pin "1") (pinfunction "B_1") (pintype "passive"))
    )
    (net (code "56") (name "Net-(T5-B)") (class "Default")
      (node (ref "R19") (pin "2") (pinfunction "2_2") (pintype "passive"))
      (node (ref "T5") (pin "1") (pinfunction "B_1") (pintype "passive"))
    )
    (net (code "57") (name "Net-(T6-B)") (class "Default")
      (node (ref "D2") (pin "A") (pinfunction "A_A") (pintype "passive"))
      (node (ref "R21") (pin "2") (pinfunction "2_2") (pintype "passive"))
      (node (ref "T6") (pin "1") (pinfunction "B_1") (pintype "passive"))
    )
    (net (code "58") (name "Net-(U1-3V3OUT)") (class "Default")
      (node (ref "C7") (pin "2") (pinfunction "2_2") (pintype "passive"))
      (node (ref "U1") (pin "17") (pinfunction "3V3OUT_17") (pintype "output"))
    )
    (net (code "59") (name "Net-(U1-CTS)") (class "Default")
      (node (ref "JP4") (pin "1") (pinfunction "1_1") (pintype "passive"))
      (node (ref "U1") (pin "11") (pinfunction "CTS_11") (pintype "input"))
    )
    (net (code "60") (name "Net-(U1-DCD)") (class "Default")
      (node (ref "JP4") (pin "2") (pinfunction "2_2") (pintype "passive"))
      (node (ref "U1") (pin "10") (pinfunction "DCD_10") (pintype "input"))
    )
    (net (code "61") (name "Net-(U1-DSR)") (class "Default")
      (node (ref "JP4") (pin "3") (pinfunction "3_3") (pintype "passive"))
      (node (ref "U1") (pin "9") (pinfunction "DSR_9") (pintype "input"))
    )
    (net (code "62") (name "Net-(U1-DTR)") (class "Default")
      (node (ref "C9") (pin "1") (pinfunction "1_1") (pintype "passive"))
      (node (ref "U1") (pin "2") (pinfunction "DTR_2") (pintype "output"))
    )
    (net (code "63") (name "Net-(U1-RESET)") (class "Default")
      (node (ref "R29") (pin "2") (pinfunction "2_2") (pintype "passive"))
      (node (ref "R30") (pin "2") (pinfunction "2_2") (pintype "passive"))
      (node (ref "U1") (pin "19") (pinfunction "RESET_19") (pintype "input"))
    )
    (net (code "64") (name "Net-(U1-RI)") (class "Default")
      (node (ref "JP4") (pin "4") (pinfunction "4_4") (pintype "passive"))
      (node (ref "U1") (pin "6") (pinfunction "RI_6") (pintype "input"))
    )
    (net (code "65") (name "Net-(U1-RTS)") (class "Default")
      (node (ref "R9") (pin "2") (pinfunction "2_2") (pintype "passive"))
      (node (ref "U1") (pin "3") (pinfunction "RTS_3") (pintype "output"))
    )
    (net (code "66") (name "Net-(U1-RXLED)") (class "Default")
      (node (ref "ON2") (pin "C") (pinfunction "C_C") (pintype "passive"))
      (node (ref "U1") (pin "22") (pinfunction "RXLED_22") (pintype "input"))
    )
    (net (code "67") (name "Net-(U1-TXLED)") (class "Default")
      (node (ref "ON1") (pin "C") (pinfunction "C_C") (pintype "passive"))
      (node (ref "U1") (pin "23") (pinfunction "TXLED_23") (pintype "input"))
    )
    (net (code "68") (name "Net-(U2-C1+)") (class "Default")
      (node (ref "C10") (pin "1") (pinfunction "1_1") (pintype "passive"))
      (node (ref "U2") (pin "1") (pinfunction "C1+_1") (pintype "bidirectional"))
    )
    (net (code "69") (name "Net-(U2-C1-)") (class "Default")
      (node (ref "C10") (pin "2") (pinfunction "2_2") (pintype "passive"))
      (node (ref "U2") (pin "3") (pinfunction "C1-_3") (pintype "bidirectional"))
    )
    (net (code "70") (name "Net-(U2-C2+)") (class "Default")
      (node (ref "C11") (pin "1") (pinfunction "1_1") (pintype "passive"))
      (node (ref "U2") (pin "4") (pinfunction "C2+_4") (pintype "bidirectional"))
    )
    (net (code "71") (name "Net-(U2-C2-)") (class "Default")
      (node (ref "C11") (pin "2") (pinfunction "2_2") (pintype "passive"))
      (node (ref "U2") (pin "5") (pinfunction "C2-_5") (pintype "bidirectional"))
    )
    (net (code "72") (name "Net-(U2-V+)") (class "Default")
      (node (ref "C13") (pin "1") (pinfunction "1_1") (pintype "passive"))
      (node (ref "U2") (pin "2") (pinfunction "V+_2") (pintype "bidirectional"))
    )
    (net (code "73") (name "Net-(U2-V-)") (class "Default")
      (node (ref "C12") (pin "1") (pinfunction "1_1") (pintype "passive"))
      (node (ref "U2") (pin "6") (pinfunction "V-_6") (pintype "bidirectional"))
    )
    (net (code "74") (name "Net-(U2-VCC)") (class "Default")
      (node (ref "C14") (pin "1") (pinfunction "1_1") (pintype "passive"))
      (node (ref "R11") (pin "1") (pinfunction "1_1") (pintype "passive"))
      (node (ref "U2") (pin "16") (pinfunction "VCC_16") (pintype "bidirectional"))
    )
    (net (code "75") (name "Net-(X4B-KL)") (class "Default")
      (node (ref "JP5") (pin "3") (pinfunction "3_3") (pintype "passive"))
      (node (ref "R24") (pin "2") (pinfunction "2_2") (pintype "passive"))
      (node (ref "X4") (pin "2") (pinfunction "KL_2") (pintype "passive"))
    )
    (net (code "76") (name "Net-(X4C-KL)") (class "Default")
      (node (ref "JP3") (pin "2") (pinfunction "2_2") (pintype "passive"))
      (node (ref "X4") (pin "3") (pinfunction "KL_3") (pintype "passive"))
      (node (ref "X5") (pin "3") (pinfunction "KL_3") (pintype "passive"))
      (node (ref "X6") (pin "3") (pinfunction "KL_3") (pintype "passive"))
    )
    (net (code "77") (name "Net-(X5B-KL)") (class "Default")
      (node (ref "JP6") (pin "3") (pinfunction "3_3") (pintype "passive"))
      (node (ref "R26") (pin "2") (pinfunction "2_2") (pintype "passive"))
      (node (ref "X5") (pin "2") (pinfunction "KL_2") (pintype "passive"))
    )
    (net (code "78") (name "Net-(X6B-KL)") (class "Default")
      (node (ref "JP8") (pin "3") (pinfunction "3_3") (pintype "passive"))
      (node (ref "R28") (pin "2") (pinfunction "2_2") (pintype "passive"))
      (node (ref "X6") (pin "2") (pinfunction "KL_2") (pintype "passive"))
    )
    (net (code "79") (name "PA0") (class "Default")
      (node (ref "IC3") (pin "78") (pinfunction "(AD0)PA0_78") (pintype "bidirectional"))
      (node (ref "JP1") (pin "33") (pinfunction "33_33") (pintype "passive"))
    )
    (net (code "80") (name "PA1") (class "Default")
      (node (ref "IC3") (pin "77") (pinfunction "(AD1)PA1_77") (pintype "bidirectional"))
      (node (ref "JP1") (pin "35") (pinfunction "35_35") (pintype "passive"))
    )
    (net (code "81") (name "PA2") (class "Default")
      (node (ref "IC3") (pin "76") (pinfunction "(AD2)PA2_76") (pintype "bidirectional"))
      (node (ref "JP1") (pin "37") (pinfunction "37_37") (pintype "passive"))
    )
    (net (code "82") (name "PA3") (class "Default")
      (node (ref "IC3") (pin "75") (pinfunction "(AD3)PA3_75") (pintype "bidirectional"))
      (node (ref "JP2") (pin "28") (pinfunction "28_28") (pintype "passive"))
    )
    (net (code "83") (name "PA4") (class "Default")
      (node (ref "IC3") (pin "74") (pinfunction "(AD4)PA4_74") (pintype "bidirectional"))
      (node (ref "JP2") (pin "26") (pinfunction "26_26") (pintype "passive"))
    )
    (net (code "84") (name "PA5") (class "Default")
      (node (ref "IC3") (pin "73") (pinfunction "(AD5)PA5_73") (pintype "bidirectional"))
      (node (ref "JP2") (pin "24") (pinfunction "24_24") (pintype "passive"))
    )
    (net (code "85") (name "PA6") (class "Default")
      (node (ref "IC3") (pin "72") (pinfunction "(AD6)PA6_72") (pintype "bidirectional"))
      (node (ref "JP2") (pin "22") (pinfunction "22_22") (pintype "passive"))
    )
    (net (code "86") (name "PA7") (class "Default")
      (node (ref "IC3") (pin "71") (pinfunction "(AD7)PA7_71") (pintype "bidirectional"))
      (node (ref "JP2") (pin "20") (pinfunction "20_20") (pintype "passive"))
    )
    (net (code "87") (name "PB0") (class "Default")
      (node (ref "IC3") (pin "19") (pinfunction "(SS/PCINT0)PB0_19") (pintype "bidirectional"))
      (node (ref "JP1") (pin "26") (pinfunction "26_26") (pintype "passive"))
      (node (ref "X9") (pin "1") (pinfunction "KL_1") (pintype "passive"))
    )
    (net (code "88") (name "PB1") (class "Default")
      (node (ref "IC3") (pin "20") (pinfunction "(SCK/PCINT1)PB1_20") (pintype "bidirectional"))
      (node (ref "ICSP") (pin "3") (pinfunction "3_3") (pintype "passive"))
      (node (ref "JP1") (pin "28") (pinfunction "28_28") (pintype "passive"))
      (node (ref "X10") (pin "3") (pinfunction "KL_3") (pintype "passive"))
    )
    (net (code "89") (name "PB2") (class "Default")
      (node (ref "IC3") (pin "21") (pinfunction "(MOSI/PCINT2)PB2_21") (pintype "bidirectional"))
      (node (ref "ICSP") (pin "4") (pinfunction "4_4") (pintype "passive"))
      (node (ref "JP1") (pin "30") (pinfunction "30_30") (pintype "passive"))
      (node (ref "X10") (pin "2") (pinfunction "KL_2") (pintype "passive"))
    )
    (net (code "90") (name "PB3") (class "Default")
      (node (ref "IC3") (pin "22") (pinfunction "(MISO/PCINT3)PB3_22") (pintype "bidirectional"))
      (node (ref "ICSP") (pin "1") (pinfunction "1_1") (pintype "passive"))
      (node (ref "JP1") (pin "32") (pinfunction "32_32") (pintype "passive"))
      (node (ref "X10") (pin "1") (pinfunction "KL_1") (pintype "passive"))
    )
    (net (code "91") (name "PB4") (class "Default")
      (node (ref "IC3") (pin "23") (pinfunction "(OC2A/PCINT4)PB4_23") (pintype "bidirectional"))
      (node (ref "JP1") (pin "34") (pinfunction "34_34") (pintype "passive"))
      (node (ref "X11") (pin "3") (pinfunction "KL_3") (pintype "passive"))
    )
    (net (code "92") (name "PB5") (class "Default")
      (node (ref "IC3") (pin "24") (pinfunction "(OC1A/PCINT5)PB5_24") (pintype "bidirectional"))
      (node (ref "JP1") (pin "36") (pinfunction "36_36") (pintype "passive"))
      (node (ref "X11") (pin "2") (pinfunction "KL_2") (pintype "passive"))
    )
    (net (code "93") (name "PB6") (class "Default")
      (node (ref "IC3") (pin "25") (pinfunction "(OC1B/PCINT6)PB6_25") (pintype "bidirectional"))
      (node (ref "JP1") (pin "38") (pinfunction "38_38") (pintype "passive"))
      (node (ref "X11") (pin "1") (pinfunction "KL_1") (pintype "passive"))
    )
    (net (code "94") (name "PB7") (class "Default")
      (node (ref "IC3") (pin "26") (pinfunction "(OC0A/OC1C/PCINT7)PB7_26") (pintype "bidirectional"))
      (node (ref "INDLED") (pin "1") (pinfunction "1_1") (pintype "passive"))
      (node (ref "JP2") (pin "27") (pinfunction "27_27") (pintype "passive"))
    )
    (net (code "95") (name "PC0") (class "Default")
      (node (ref "IC3") (pin "53") (pinfunction "(A8)PC0_53") (pintype "bidirectional"))
      (node (ref "JP2") (pin "3") (pinfunction "3_3") (pintype "passive"))
    )
    (net (code "96") (name "PC1") (class "Default")
      (node (ref "IC3") (pin "54") (pinfunction "(A9)PC1_54") (pintype "bidirectional"))
      (node (ref "JP2") (pin "1") (pinfunction "1_1") (pintype "passive"))
    )
    (net (code "97") (name "PC2") (class "Default")
      (node (ref "IC3") (pin "55") (pinfunction "(A10)PC2_55") (pintype "bidirectional"))
      (node (ref "JP2") (pin "2") (pinfunction "2_2") (pintype "passive"))
    )
    (net (code "98") (name "PC3") (class "Default")
      (node (ref "IC3") (pin "56") (pinfunction "(A11)PC3_56") (pintype "bidirectional"))
      (node (ref "JP2") (pin "4") (pinfunction "4_4") (pintype "passive"))
    )
    (net (code "99") (name "PC4") (class "Default")
      (node (ref "IC3") (pin "57") (pinfunction "(A12)PC4_57") (pintype "bidirectional"))
      (node (ref "JP2") (pin "6") (pinfunction "6_6") (pintype "passive"))
    )
    (net (code "100") (name "PC5") (class "Default")
      (node (ref "IC3") (pin "58") (pinfunction "(A13)PC5_58") (pintype "bidirectional"))
      (node (ref "JP2") (pin "8") (pinfunction "8_8") (pintype "passive"))
    )
    (net (code "101") (name "PC6") (class "Default")
      (node (ref "IC3") (pin "59") (pinfunction "(A14)PC6_59") (pintype "bidirectional"))
      (node (ref "JP2") (pin "10") (pinfunction "10_10") (pintype "passive"))
    )
    (net (code "102") (name "PC7") (class "Default")
      (node (ref "IC3") (pin "60") (pinfunction "(A15)PC7_60") (pintype "bidirectional"))
      (node (ref "JP2") (pin "12") (pinfunction "12_12") (pintype "passive"))
    )
    (net (code "103") (name "PD7") (class "Default")
      (node (ref "IC3") (pin "50") (pinfunction "(T0)PD7_50") (pintype "bidirectional"))
      (node (ref "JP2") (pin "9") (pinfunction "9_9") (pintype "passive"))
    )
    (net (code "104") (name "PG0") (class "Default")
      (node (ref "IC3") (pin "51") (pinfunction "(WR)PG0_51") (pintype "bidirectional"))
      (node (ref "JP2") (pin "7") (pinfunction "7_7") (pintype "passive"))
    )
    (net (code "105") (name "PG1") (class "Default")
      (node (ref "IC3") (pin "52") (pinfunction "(RD)PG1_52") (pintype "bidirectional"))
      (node (ref "JP2") (pin "5") (pinfunction "5_5") (pintype "passive"))
    )
    (net (code "106") (name "PG2") (class "Default")
      (node (ref "IC3") (pin "70") (pinfunction "(ALE)PG2_70") (pintype "bidirectional"))
      (node (ref "JP2") (pin "18") (pinfunction "18_18") (pintype "passive"))
    )
    (net (code "107") (name "PL0") (class "Default")
      (node (ref "IC3") (pin "35") (pinfunction "PL0(ICP4)_35") (pintype "bidirectional"))
    )
    (net (code "108") (name "PL1") (class "Default")
      (node (ref "IC3") (pin "36") (pinfunction "PL1(ICP5)_36") (pintype "bidirectional"))
    )
    (net (code "109") (name "PL2") (class "Default")
      (node (ref "IC3") (pin "37") (pinfunction "PL2(T5)_37") (pintype "bidirectional"))
      (node (ref "JP2") (pin "25") (pinfunction "25_25") (pintype "passive"))
      (node (ref "JP8") (pin "2") (pinfunction "2_2") (pintype "passive"))
    )
    (net (code "110") (name "PL3") (class "Default")
      (node (ref "IC3") (pin "38") (pinfunction "PL3(OC5A)_38") (pintype "bidirectional"))
      (node (ref "JP2") (pin "23") (pinfunction "23_23") (pintype "passive"))
      (node (ref "JP6") (pin "2") (pinfunction "2_2") (pintype "passive"))
    )
    (net (code "111") (name "PL4") (class "Default")
      (node (ref "IC3") (pin "39") (pinfunction "PL4(OC5B)_39") (pintype "bidirectional"))
      (node (ref "JP2") (pin "21") (pinfunction "21_21") (pintype "passive"))
      (node (ref "JP5") (pin "2") (pinfunction "2_2") (pintype "passive"))
    )
    (net (code "112") (name "PL5") (class "Default")
      (node (ref "IC3") (pin "40") (pinfunction "PL5(OC5C)_40") (pintype "bidirectional"))
      (node (ref "JP2") (pin "19") (pinfunction "19_19") (pintype "passive"))
    )
    (net (code "113") (name "PL6") (class "Default")
      (node (ref "IC3") (pin "41") (pinfunction "PL6_41") (pintype "bidirectional"))
    )
    (net (code "114") (name "PL7") (class "Default")
      (node (ref "IC3") (pin "42") (pinfunction "PL7_42") (pintype "bidirectional"))
    )
    (net (code "115") (name "R1IN") (class "Default")
      (node (ref "R13") (pin "1") (pinfunction "1_1") (pintype "passive"))
      (node (ref "T4") (pin "2") (pinfunction "E_2") (pintype "passive"))
      (node (ref "U2") (pin "8") (pinfunction "R2IN_8") (pintype "input"))
    )
    (net (code "116") (name "R1IN_") (class "Default")
      (node (ref "T4") (pin "3") (pinfunction "C_3") (pintype "passive"))
      (node (ref "X1") (pin "2") (pinfunction "KL_2") (pintype "passive"))
    )
    (net (code "117") (name "R1OUT") (class "Default")
      (node (ref "JP7") (pin "8") (pinfunction "8_8") (pintype "passive"))
      (node (ref "U2") (pin "9") (pinfunction "R2OUT_9") (pintype "output"))
    )
    (net (code "118") (name "R2IN") (class "Default")
      (node (ref "R14") (pin "1") (pinfunction "1_1") (pintype "passive"))
      (node (ref "T2") (pin "2") (pinfunction "E_2") (pintype "passive"))
      (node (ref "U2") (pin "13") (pinfunction "R1IN_13") (pintype "input"))
    )
    (net (code "119") (name "R2IN_") (class "Default")
      (node (ref "T2") (pin "3") (pinfunction "C_3") (pintype "passive"))
      (node (ref "X1") (pin "3") (pinfunction "KL_3") (pintype "passive"))
    )
    (net (code "120") (name "R2OUT") (class "Default")
      (node (ref "JP7") (pin "6") (pinfunction "6_6") (pintype "passive"))
      (node (ref "U2") (pin "12") (pinfunction "R1OUT_12") (pintype "output"))
    )
    (net (code "121") (name "REG_5V") (class "Default")
      (node (ref "C18") (pin "2") (pinfunction "2_2") (pintype "passive"))
      (node (ref "PC2") (pin "+") (pinfunction "+_+") (pintype "passive"))
      (node (ref "POWER") (pin "2") (pinfunction "2_2") (pintype "passive"))
      (node (ref "POWER") (pin "5") (pinfunction "5_5") (pintype "passive"))
      (node (ref "SJ1") (pin "3") (pinfunction "3_3") (pintype "passive"))
      (node (ref "U4") (pin "2") (pinfunction "OUT_2") (pintype "passive"))
      (node (ref "U4") (pin "4") (pinfunction "OUT_4") (pintype "passive"))
    )
    (net (code "122") (name "RESET") (class "Default")
      (node (ref "C1") (pin "1") (pinfunction "1_1") (pintype "passive"))
      (node (ref "C9") (pin "2") (pinfunction "2_2") (pintype "passive"))
      (node (ref "D3") (pin "A") (pinfunction "A_A") (pintype "passive"))
      (node (ref "IC3") (pin "30") (pinfunction "RESET_30") (pintype "input"))
      (node (ref "ICSP") (pin "5") (pinfunction "5_5") (pintype "passive"))
      (node (ref "POWER") (pin "3") (pinfunction "3_3") (pintype "passive"))
      (node (ref "R4") (pin "1") (pinfunction "1_1") (pintype "passive"))
      (node (ref "R9") (pin "1") (pinfunction "1_1") (pintype "passive"))
      (node (ref "S1") (pin "1") (pinfunction "1_1") (pintype "passive"))
    )
    (net (code "123") (name "RXD1") (class "Default")
      (node (ref "IC3") (pin "45") (pinfunction "(RXD1/INT2)PD2_45") (pintype "bidirectional"))
      (node (ref "JP2") (pin "13") (pinfunction "13_13") (pintype "passive"))
      (node (ref "JP7") (pin "5") (pinfunction "5_5") (pintype "passive"))
    )
    (net (code "124") (name "RXD2") (class "Default")
      (node (ref "IC3") (pin "12") (pinfunction "PH0(RXD2)_12") (pintype "bidirectional"))
      (node (ref "JP1") (pin "14") (pinfunction "14_14") (pintype "passive"))
    )
    (net (code "125") (name "RXD3") (class "Default")
      (node (ref "IC3") (pin "63") (pinfunction "PJ0(RXD3/PCINT9)_63") (pintype "bidirectional"))
      (node (ref "JP2") (pin "14") (pinfunction "14_14") (pintype "passive"))
      (node (ref "JP7") (pin "7") (pinfunction "7_7") (pintype "passive"))
    )
    (net (code "126") (name "SCL") (class "Default")
      (node (ref "IC3") (pin "43") (pinfunction "(SCL/INT0)PD0_43") (pintype "bidirectional"))
      (node (ref "JP2") (pin "17") (pinfunction "17_17") (pintype "passive"))
      (node (ref "R2") (pin "1") (pinfunction "1_1") (pintype "passive"))
    )
    (net (code "127") (name "SDA") (class "Default")
      (node (ref "IC3") (pin "44") (pinfunction "(SDA/INT1)PD1_44") (pintype "bidirectional"))
      (node (ref "JP2") (pin "15") (pinfunction "15_15") (pintype "passive"))
      (node (ref "R3") (pin "1") (pinfunction "1_1") (pintype "passive"))
    )
    (net (code "128") (name "T1IN") (class "Default")
      (node (ref "JP7") (pin "4") (pinfunction "4_4") (pintype "passive"))
      (node (ref "R10") (pin "1") (pinfunction "1_1") (pintype "passive"))
      (node (ref "U2") (pin "10") (pinfunction "T2IN_10") (pintype "input"))
    )
    (net (code "129") (name "T1OUT") (class "Default")
      (node (ref "T3") (pin "2") (pinfunction "E_2") (pintype "passive"))
      (node (ref "U2") (pin "7") (pinfunction "T2OUT_7") (pintype "output"))
    )
    (net (code "130") (name "T1OUT_") (class "Default")
      (node (ref "T3") (pin "3") (pinfunction "C_3") (pintype "passive"))
      (node (ref "X1") (pin "4") (pinfunction "KL_4") (pintype "passive"))
    )
    (net (code "131") (name "T2IN") (class "Default")
      (node (ref "JP7") (pin "2") (pinfunction "2_2") (pintype "passive"))
      (node (ref "R12") (pin "1") (pinfunction "1_1") (pintype "passive"))
      (node (ref "U2") (pin "11") (pinfunction "T1IN_11") (pintype "input"))
    )
    (net (code "132") (name "T2OUT") (class "Default")
      (node (ref "T1") (pin "2") (pinfunction "E_2") (pintype "passive"))
      (node (ref "U2") (pin "14") (pinfunction "T1OUT_14") (pintype "output"))
    )
    (net (code "133") (name "T2OUT_") (class "Default")
      (node (ref "T1") (pin "3") (pinfunction "C_3") (pintype "passive"))
      (node (ref "X1") (pin "5") (pinfunction "KL_5") (pintype "passive"))
    )
    (net (code "134") (name "TXD1") (class "Default")
      (node (ref "IC3") (pin "46") (pinfunction "(TXD1/INT3)PD3_46") (pintype "bidirectional"))
      (node (ref "JP2") (pin "11") (pinfunction "11_11") (pintype "passive"))
      (node (ref "JP7") (pin "1") (pinfunction "1_1") (pintype "passive"))
    )
    (net (code "135") (name "TXD2") (class "Default")
      (node (ref "IC3") (pin "13") (pinfunction "PH1(TXD2)_13") (pintype "bidirectional"))
      (node (ref "JP1") (pin "16") (pinfunction "16_16") (pintype "passive"))
    )
    (net (code "136") (name "TXD3") (class "Default")
      (node (ref "IC3") (pin "64") (pinfunction "PJ1(TXD3/PCINT10)_64") (pintype "bidirectional"))
      (node (ref "JP2") (pin "16") (pinfunction "16_16") (pintype "passive"))
      (node (ref "JP7") (pin "3") (pinfunction "3_3") (pintype "passive"))
    )
    (net (code "137") (name "VIN") (class "Default")
      (node (ref "JP3") (pin "1") (pinfunction "1_1") (pintype "passive"))
      (node (ref "LM2576-12V") (pin "P$1") (pinfunction "+V_IN_P$1") (pintype "input"))
      (node (ref "PC3") (pin "+") (pinfunction "+_+") (pintype "passive"))
      (node (ref "POWER") (pin "8") (pinfunction "8_8") (pintype "passive"))
      (node (ref "R20") (pin "2") (pinfunction "2_2") (pintype "passive"))
      (node (ref "T6") (pin "3") (pinfunction "C_3") (pintype "passive"))
      (node (ref "X3") (pin "2") (pinfunction "2_2") (pintype "power_in"))
      (node (ref "X7") (pin "2") (pinfunction "KL_2") (pintype "passive"))
      (node (ref "X8") (pin "3") (pinfunction "KL_3") (pintype "passive"))
    )
    (net (code "138") (name "XTAL1") (class "Default")
      (node (ref "IC3") (pin "34") (pinfunction "XTAL1_34") (pintype "input"))
      (node (ref "R1") (pin "1") (pinfunction "1_1") (pintype "passive"))
      (node (ref "Y1") (pin "3") (pinfunction "3_3") (pintype "passive"))
    )
    (net (code "139") (name "XTAL2") (class "Default")
      (node (ref "IC3") (pin "33") (pinfunction "XTAL2_33") (pintype "output"))
      (node (ref "R1") (pin "2") (pinfunction "2_2") (pintype "passive"))
      (node (ref "Y1") (pin "1") (pinfunction "1_1") (pintype "passive"))
    )
    (net (code "140") (name "unconnected-(H1-MOUNT-PadB3,2)") (class "Default")
      (node (ref "H1") (pin "B3,2") (pinfunction "MOUNT_B3,2") (pintype "passive"))
    )
    (net (code "141") (name "unconnected-(H2-MOUNT-PadB3,2)") (class "Default")
      (node (ref "H2") (pin "B3,2") (pinfunction "MOUNT_B3,2") (pintype "passive"))
    )
    (net (code "142") (name "unconnected-(H4-MOUNT-PadB3,2)") (class "Default")
      (node (ref "H4") (pin "B3,2") (pinfunction "MOUNT_B3,2") (pintype "passive"))
    )
    (net (code "143") (name "unconnected-(IC3-(CLKO{slash}ICP3{slash}INT7)PE7-Pad9)") (class "Default")
      (node (ref "IC3") (pin "9") (pinfunction "(CLKO/ICP3/INT7)PE7_9") (pintype "bidirectional"))
    )
    (net (code "144") (name "unconnected-(IC3-(ICP1)PD4-Pad47)") (class "Default")
      (node (ref "IC3") (pin "47") (pinfunction "(ICP1)PD4_47") (pintype "bidirectional"))
    )
    (net (code "145") (name "unconnected-(IC3-(T1)PD6-Pad49)") (class "Default")
      (node (ref "IC3") (pin "49") (pinfunction "(T1)PD6_49") (pintype "bidirectional"))
    )
    (net (code "146") (name "unconnected-(IC3-(T3{slash}INT6)PE6-Pad8)") (class "Default")
      (node (ref "IC3") (pin "8") (pinfunction "(T3/INT6)PE6_8") (pintype "bidirectional"))
    )
    (net (code "147") (name "unconnected-(IC3-(TOSC1)PG4-Pad29)") (class "Default")
      (node (ref "IC3") (pin "29") (pinfunction "(TOSC1)PG4_29") (pintype "bidirectional"))
    )
    (net (code "148") (name "unconnected-(IC3-(TOSC2)PG3-Pad28)") (class "Default")
      (node (ref "IC3") (pin "28") (pinfunction "(TOSC2)PG3_28") (pintype "bidirectional"))
    )
    (net (code "149") (name "unconnected-(IC3-(XCK0{slash}AIN0)PE2-Pad4)") (class "Default")
      (node (ref "IC3") (pin "4") (pinfunction "(XCK0/AIN0)PE2_4") (pintype "bidirectional"))
    )
    (net (code "150") (name "unconnected-(IC3-(XCK1)PD5-Pad48)") (class "Default")
      (node (ref "IC3") (pin "48") (pinfunction "(XCK1)PD5_48") (pintype "bidirectional"))
    )
    (net (code "151") (name "unconnected-(IC3-PH2(XCK2)-Pad14)") (class "Default")
      (node (ref "IC3") (pin "14") (pinfunction "PH2(XCK2)_14") (pintype "bidirectional"))
    )
    (net (code "152") (name "unconnected-(IC3-PH7(T4)-Pad27)") (class "Default")
      (node (ref "IC3") (pin "27") (pinfunction "PH7(T4)_27") (pintype "bidirectional"))
    )
    (net (code "153") (name "unconnected-(IC3-PJ2(XCK3{slash}PCINT11)-Pad65)") (class "Default")
      (node (ref "IC3") (pin "65") (pinfunction "PJ2(XCK3/PCINT11)_65") (pintype "bidirectional"))
    )
    (net (code "154") (name "unconnected-(IC3-PJ3(PCINT12)-Pad66)") (class "Default")
      (node (ref "IC3") (pin "66") (pinfunction "PJ3(PCINT12)_66") (pintype "bidirectional"))
    )
    (net (code "155") (name "unconnected-(IC3-PJ4(PCINT13)-Pad67)") (class "Default")
      (node (ref "IC3") (pin "67") (pinfunction "PJ4(PCINT13)_67") (pintype "bidirectional"))
    )
    (net (code "156") (name "unconnected-(IC3-PJ5(PCINT14)-Pad68)") (class "Default")
      (node (ref "IC3") (pin "68") (pinfunction "PJ5(PCINT14)_68") (pintype "bidirectional"))
    )
    (net (code "157") (name "unconnected-(IC3-PJ6(PCINT15)-Pad69)") (class "Default")
      (node (ref "IC3") (pin "69") (pinfunction "PJ6(PCINT15)_69") (pintype "bidirectional"))
    )
    (net (code "158") (name "unconnected-(IC3-PJ7-Pad79)") (class "Default")
      (node (ref "IC3") (pin "79") (pinfunction "PJ7_79") (pintype "bidirectional"))
    )
    (net (code "159") (name "unconnected-(U1-OSCI-Pad27)") (class "Default")
      (node (ref "U1") (pin "27") (pinfunction "OSCI_27") (pintype "input"))
    )
    (net (code "160") (name "unconnected-(U1-OSCO-Pad28)") (class "Default")
      (node (ref "U1") (pin "28") (pinfunction "OSCO_28") (pintype "output"))
    )
    (net (code "161") (name "unconnected-(U1-PWREN-Pad14)") (class "Default")
      (node (ref "U1") (pin "14") (pinfunction "PWREN_14") (pintype "input"))
    )
    (net (code "162") (name "unconnected-(U1-SLEEP-Pad12)") (class "Default")
      (node (ref "U1") (pin "12") (pinfunction "SLEEP_12") (pintype "input"))
    )
    (net (code "163") (name "unconnected-(U1-TXDEN-Pad13)") (class "Default")
      (node (ref "U1") (pin "13") (pinfunction "TXDEN_13") (pintype "input"))
    )
  )
)
